# usbdist.net
KiCad netlist of a schematic drawn in EAGLE
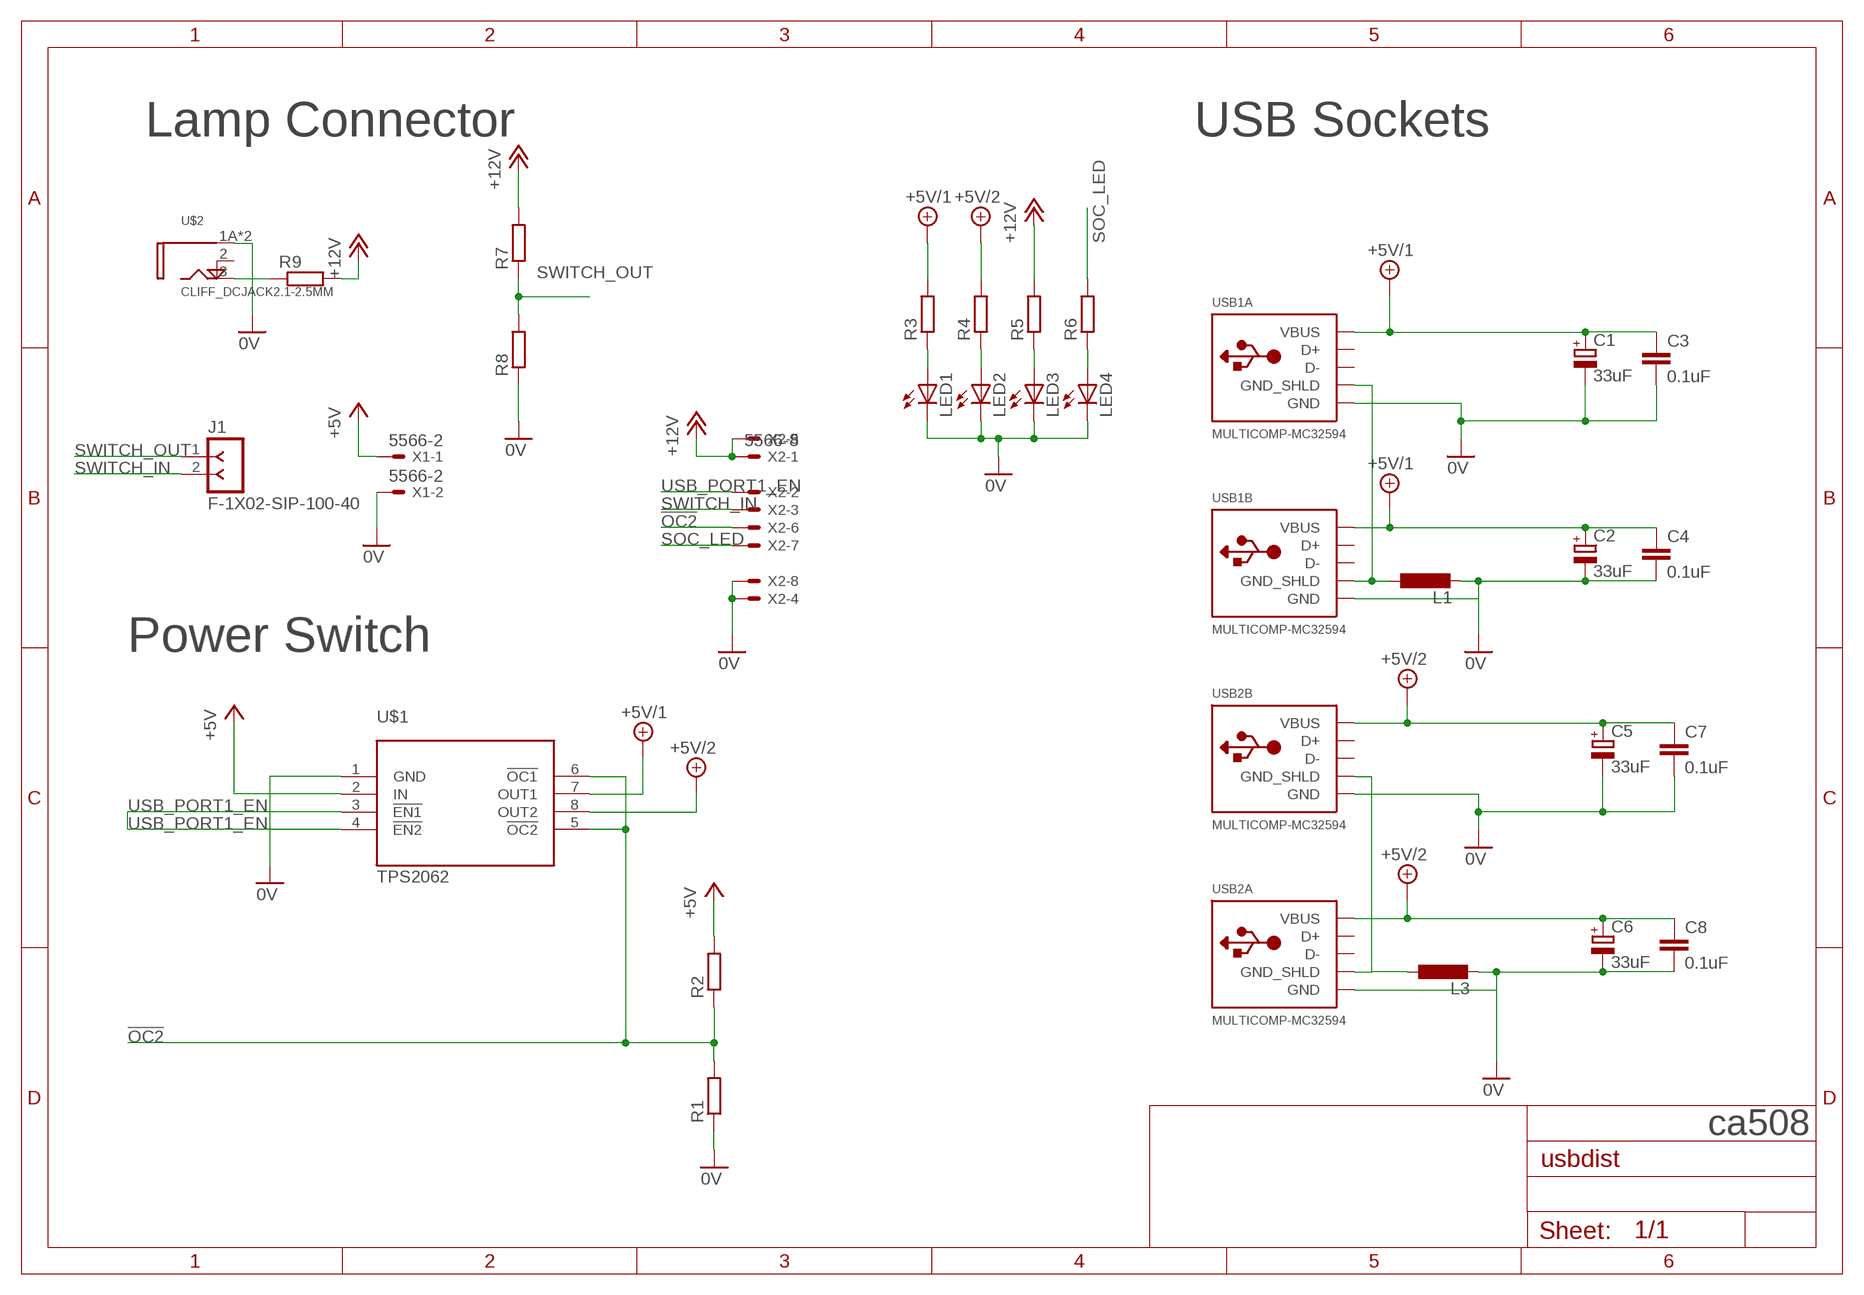
[diagram p0: schematic, sheet 1]

(export (version "E")
  (design (tool "Eeschema 10.0.6"))
  (components
    (comp (ref "C1")
      (value "33uF")
      (footprint "eagle-import:B_3528-21R")
      (libsource (lib "eagle-import") (part "CPOL-EUB/3528-21R"))
    )
    (comp (ref "C2")
      (value "33uF")
      (footprint "eagle-import:B_3528-21R")
      (libsource (lib "eagle-import") (part "CPOL-EUB/3528-21R"))
    )
    (comp (ref "C3")
      (value "0.1uF")
      (footprint "eagle-import:C0603")
      (libsource (lib "eagle-import") (part "C-EUC0603"))
    )
    (comp (ref "C4")
      (value "0.1uF")
      (footprint "eagle-import:C0603")
      (libsource (lib "eagle-import") (part "C-EUC0603"))
    )
    (comp (ref "C5")
      (value "33uF")
      (footprint "eagle-import:B_3528-21R")
      (libsource (lib "eagle-import") (part "CPOL-EUB/3528-21R"))
    )
    (comp (ref "C6")
      (value "33uF")
      (footprint "eagle-import:B_3528-21R")
      (libsource (lib "eagle-import") (part "CPOL-EUB/3528-21R"))
    )
    (comp (ref "C7")
      (value "0.1uF")
      (footprint "eagle-import:C0603")
      (libsource (lib "eagle-import") (part "C-EUC0603"))
    )
    (comp (ref "C8")
      (value "0.1uF")
      (footprint "eagle-import:C0603")
      (libsource (lib "eagle-import") (part "C-EUC0603"))
    )
    (comp (ref "J1")
      (value "F-1X02-SIP-100-40")
      (footprint "eagle-import:SIP-100-02-40")
      (libsource (lib "eagle-import") (part "F-1X02-SIP-100-40"))
    )
    (comp (ref "L1")
      (value "L-EUL2012C")
      (footprint "eagle-import:L2012C")
      (libsource (lib "eagle-import") (part "L-EUL2012C"))
    )
    (comp (ref "L3")
      (value "L-EUL2012C")
      (footprint "eagle-import:L2012C")
      (libsource (lib "eagle-import") (part "L-EUL2012C"))
    )
    (comp (ref "LED1")
      (value "LEDCHIP-LED0805")
      (footprint "eagle-import:CHIP-LED0805")
      (libsource (lib "eagle-import") (part "LEDCHIP-LED0805"))
    )
    (comp (ref "LED2")
      (value "LEDCHIP-LED0805")
      (footprint "eagle-import:CHIP-LED0805")
      (libsource (lib "eagle-import") (part "LEDCHIP-LED0805"))
    )
    (comp (ref "LED3")
      (value "LEDCHIP-LED0805")
      (footprint "eagle-import:CHIP-LED0805")
      (libsource (lib "eagle-import") (part "LEDCHIP-LED0805"))
    )
    (comp (ref "LED4")
      (value "LEDCHIP-LED0805")
      (footprint "eagle-import:CHIP-LED0805")
      (libsource (lib "eagle-import") (part "LEDCHIP-LED0805"))
    )
    (comp (ref "R1")
      (value "R-EU_R0805")
      (footprint "eagle-import:R0805")
      (libsource (lib "eagle-import") (part "R-EU_R0805"))
    )
    (comp (ref "R2")
      (value "R-EU_R0805")
      (footprint "eagle-import:R0805")
      (libsource (lib "eagle-import") (part "R-EU_R0805"))
    )
    (comp (ref "R3")
      (value "R-EU_R0805")
      (footprint "eagle-import:R0805")
      (libsource (lib "eagle-import") (part "R-EU_R0805"))
    )
    (comp (ref "R4")
      (value "R-EU_R0805")
      (footprint "eagle-import:R0805")
      (libsource (lib "eagle-import") (part "R-EU_R0805"))
    )
    (comp (ref "R5")
      (value "R-EU_R0805")
      (footprint "eagle-import:R0805")
      (libsource (lib "eagle-import") (part "R-EU_R0805"))
    )
    (comp (ref "R6")
      (value "R-EU_R0805")
      (footprint "eagle-import:R0805")
      (libsource (lib "eagle-import") (part "R-EU_R0805"))
    )
    (comp (ref "R7")
      (value "R-EU_R0805")
      (footprint "eagle-import:R0805")
      (libsource (lib "eagle-import") (part "R-EU_R0805"))
    )
    (comp (ref "R8")
      (value "R-EU_R0805")
      (footprint "eagle-import:R0805")
      (libsource (lib "eagle-import") (part "R-EU_R0805"))
    )
    (comp (ref "R9")
      (value "R-EU_0204/5")
      (footprint "eagle-import:0204_5")
      (libsource (lib "eagle-import") (part "R-EU_0204/5"))
    )
    (comp (ref "U$1")
      (value "TPS2062")
      (footprint "eagle-import:SO8")
      (libsource (lib "eagle-import") (part "TPS2062"))
    )
    (comp (ref "U$2")
      (value "CLIFF_DCJACK2.1-2.5MM")
      (footprint "eagle-import:FC6814XS")
      (libsource (lib "eagle-import") (part "CLIFF_DCJACK2.1-2.5MM"))
    )
    (comp (ref "USB1")
      (value "MULTICOMP-MC32594")
      (footprint "eagle-import:MC32594")
      (libsource (lib "eagle-import") (part "MULTICOMP-MC32594"))
    )
    (comp (ref "USB2")
      (value "MULTICOMP-MC32594")
      (footprint "eagle-import:MC32594")
      (libsource (lib "eagle-import") (part "MULTICOMP-MC32594"))
    )
    (comp (ref "X1")
      (value "5566-2")
      (footprint "eagle-import:5566-2")
      (libsource (lib "eagle-import") (part "5566-2"))
    )
    (comp (ref "X2")
      (value "5566-8")
      (footprint "eagle-import:5566-8")
      (libsource (lib "eagle-import") (part "5566-8"))
    )
  )
  (nets
    (net (code "1") (name "+5V") (class "Default")
      (node (ref "R2") (pin "2") (pinfunction "2_2") (pintype "passive"))
      (node (ref "U$1") (pin "2") (pinfunction "IN_2") (pintype "input"))
      (node (ref "X1") (pin "1") (pinfunction "S_1") (pintype "passive"))
    )
    (net (code "2") (name "+5V{slash}1") (class "Default")
      (node (ref "C1") (pin "+") (pinfunction "+_+") (pintype "passive"))
      (node (ref "C2") (pin "+") (pinfunction "+_+") (pintype "passive"))
      (node (ref "C3") (pin "1") (pinfunction "1_1") (pintype "passive"))
      (node (ref "C4") (pin "1") (pinfunction "1_1") (pintype "passive"))
      (node (ref "R3") (pin "2") (pinfunction "2_2") (pintype "passive"))
      (node (ref "U$1") (pin "7") (pinfunction "OUT1_7") (pintype "passive"))
      (node (ref "USB1") (pin "USB1-1") (pinfunction "VBUS_USB1-1") (pintype "power_in"))
      (node (ref "USB1") (pin "USB2-1") (pinfunction "VBUS_USB2-1") (pintype "power_in"))
    )
    (net (code "3") (name "+5V{slash}2") (class "Default")
      (node (ref "C5") (pin "+") (pinfunction "+_+") (pintype "passive"))
      (node (ref "C6") (pin "+") (pinfunction "+_+") (pintype "passive"))
      (node (ref "C7") (pin "1") (pinfunction "1_1") (pintype "passive"))
      (node (ref "C8") (pin "1") (pinfunction "1_1") (pintype "passive"))
      (node (ref "R4") (pin "2") (pinfunction "2_2") (pintype "passive"))
      (node (ref "U$1") (pin "8") (pinfunction "OUT2_8") (pintype "passive"))
      (node (ref "USB2") (pin "USB1-1") (pinfunction "VBUS_USB1-1") (pintype "power_in"))
      (node (ref "USB2") (pin "USB2-1") (pinfunction "VBUS_USB2-1") (pintype "power_in"))
    )
    (net (code "4") (name "+12V") (class "Default")
      (node (ref "R5") (pin "2") (pinfunction "2_2") (pintype "passive"))
      (node (ref "R7") (pin "2") (pinfunction "2_2") (pintype "passive"))
      (node (ref "R9") (pin "2") (pinfunction "2_2") (pintype "passive"))
      (node (ref "X2") (pin "1") (pinfunction "S_1") (pintype "passive"))
      (node (ref "X2") (pin "5") (pinfunction "S_5") (pintype "passive"))
    )
    (net (code "5") (name "/SHUNT") (class "Default")
      (node (ref "U$2") (pin "2") (pinfunction "SHUNT_2") (pintype "power_in"))
    )
    (net (code "6") (name "/SOC_LED") (class "Default")
      (node (ref "R6") (pin "2") (pinfunction "2_2") (pintype "passive"))
      (node (ref "X2") (pin "7") (pinfunction "S_7") (pintype "passive"))
    )
    (net (code "7") (name "/SWITCH_IN") (class "Default")
      (node (ref "J1") (pin "2") (pinfunction "2_2") (pintype "passive"))
      (node (ref "X2") (pin "3") (pinfunction "S_3") (pintype "passive"))
    )
    (net (code "8") (name "/SWITCH_OUT") (class "Default")
      (node (ref "J1") (pin "1") (pinfunction "1_1") (pintype "passive"))
      (node (ref "R7") (pin "1") (pinfunction "1_1") (pintype "passive"))
      (node (ref "R8") (pin "2") (pinfunction "2_2") (pintype "passive"))
    )
    (net (code "9") (name "/USB_PORT1_EN") (class "Default")
      (node (ref "U$1") (pin "3") (pinfunction "~{EN1}_3") (pintype "input"))
      (node (ref "U$1") (pin "4") (pinfunction "~{EN2}_4") (pintype "input"))
      (node (ref "X2") (pin "2") (pinfunction "S_2") (pintype "passive"))
    )
    (net (code "10") (name "/~{OC2}") (class "Default")
      (node (ref "R1") (pin "2") (pinfunction "2_2") (pintype "passive"))
      (node (ref "R2") (pin "1") (pinfunction "1_1") (pintype "passive"))
      (node (ref "U$1") (pin "5") (pinfunction "~{OC2}_5") (pintype "power_in"))
      (node (ref "U$1") (pin "6") (pinfunction "~{OC1}_6") (pintype "passive"))
      (node (ref "X2") (pin "6") (pinfunction "S_6") (pintype "passive"))
    )
    (net (code "11") (name "0V") (class "Default")
      (node (ref "C1") (pin "-") (pinfunction "-_-") (pintype "passive"))
      (node (ref "C2") (pin "-") (pinfunction "-_-") (pintype "passive"))
      (node (ref "C3") (pin "2") (pinfunction "2_2") (pintype "passive"))
      (node (ref "C4") (pin "2") (pinfunction "2_2") (pintype "passive"))
      (node (ref "C5") (pin "-") (pinfunction "-_-") (pintype "passive"))
      (node (ref "C6") (pin "-") (pinfunction "-_-") (pintype "passive"))
      (node (ref "C7") (pin "2") (pinfunction "2_2") (pintype "passive"))
      (node (ref "C8") (pin "2") (pinfunction "2_2") (pintype "passive"))
      (node (ref "L1") (pin "2") (pinfunction "2_2") (pintype "passive"))
      (node (ref "L3") (pin "2") (pinfunction "2_2") (pintype "passive"))
      (node (ref "LED1") (pin "C") (pinfunction "C_C") (pintype "passive"))
      (node (ref "LED2") (pin "C") (pinfunction "C_C") (pintype "passive"))
      (node (ref "LED3") (pin "C") (pinfunction "C_C") (pintype "passive"))
      (node (ref "LED4") (pin "C") (pinfunction "C_C") (pintype "passive"))
      (node (ref "R1") (pin "1") (pinfunction "1_1") (pintype "passive"))
      (node (ref "R8") (pin "1") (pinfunction "1_1") (pintype "passive"))
      (node (ref "U$1") (pin "1") (pinfunction "GND_1") (pintype "input"))
      (node (ref "U$2") (pin "1A") (pinfunction "SLEEVE_1A") (pintype "power_in"))
      (node (ref "U$2") (pin "1B") (pinfunction "SLEEVE_1B") (pintype "power_in"))
      (node (ref "USB1") (pin "USB1-4") (pinfunction "GND_USB1-4") (pintype "power_in"))
      (node (ref "USB1") (pin "USB2-4") (pinfunction "GND_USB2-4") (pintype "power_in"))
      (node (ref "USB2") (pin "USB1-4") (pinfunction "GND_USB1-4") (pintype "power_in"))
      (node (ref "USB2") (pin "USB2-4") (pinfunction "GND_USB2-4") (pintype "power_in"))
      (node (ref "X1") (pin "2") (pinfunction "S_2") (pintype "passive"))
      (node (ref "X2") (pin "4") (pinfunction "S_4") (pintype "passive"))
      (node (ref "X2") (pin "8") (pinfunction "S_8") (pintype "passive"))
    )
    (net (code "12") (name "Net-(L1-Pad1)") (class "Default")
      (node (ref "L1") (pin "1") (pinfunction "1_1") (pintype "passive"))
      (node (ref "USB1") (pin "P$1") (pinfunction "GND_SHLD_P$1") (pintype "power_in"))
      (node (ref "USB1") (pin "P$2") (pinfunction "GND_SHLD_P$2") (pintype "power_in"))
      (node (ref "USB1") (pin "P$3") (pinfunction "GND_SHLD_P$3") (pintype "power_in"))
      (node (ref "USB1") (pin "P$4") (pinfunction "GND_SHLD_P$4") (pintype "power_in"))
    )
    (net (code "13") (name "Net-(L3-Pad1)") (class "Default")
      (node (ref "L3") (pin "1") (pinfunction "1_1") (pintype "passive"))
      (node (ref "USB2") (pin "P$1") (pinfunction "GND_SHLD_P$1") (pintype "power_in"))
      (node (ref "USB2") (pin "P$2") (pinfunction "GND_SHLD_P$2") (pintype "power_in"))
      (node (ref "USB2") (pin "P$3") (pinfunction "GND_SHLD_P$3") (pintype "power_in"))
      (node (ref "USB2") (pin "P$4") (pinfunction "GND_SHLD_P$4") (pintype "power_in"))
    )
    (net (code "14") (name "Net-(LED1-PadA)") (class "Default")
      (node (ref "LED1") (pin "A") (pinfunction "A_A") (pintype "passive"))
      (node (ref "R3") (pin "1") (pinfunction "1_1") (pintype "passive"))
    )
    (net (code "15") (name "Net-(LED2-PadA)") (class "Default")
      (node (ref "LED2") (pin "A") (pinfunction "A_A") (pintype "passive"))
      (node (ref "R4") (pin "1") (pinfunction "1_1") (pintype "passive"))
    )
    (net (code "16") (name "Net-(LED3-PadA)") (class "Default")
      (node (ref "LED3") (pin "A") (pinfunction "A_A") (pintype "passive"))
      (node (ref "R5") (pin "1") (pinfunction "1_1") (pintype "passive"))
    )
    (net (code "17") (name "Net-(LED4-PadA)") (class "Default")
      (node (ref "LED4") (pin "A") (pinfunction "A_A") (pintype "passive"))
      (node (ref "R6") (pin "1") (pinfunction "1_1") (pintype "passive"))
    )
    (net (code "18") (name "Net-(U$2-TIP)") (class "Default")
      (node (ref "R9") (pin "1") (pinfunction "1_1") (pintype "passive"))
      (node (ref "U$2") (pin "3") (pinfunction "TIP_3") (pintype "power_in"))
    )
    (net (code "19") (name "unconnected-(USB1A-D+-PadUSB1-3)") (class "Default")
      (node (ref "USB1") (pin "USB1-3") (pinfunction "D+_USB1-3") (pintype "bidirectional"))
    )
    (net (code "20") (name "unconnected-(USB1A-D--PadUSB1-2)") (class "Default")
      (node (ref "USB1") (pin "USB1-2") (pinfunction "D-_USB1-2") (pintype "bidirectional"))
    )
    (net (code "21") (name "unconnected-(USB1B-D+-PadUSB2-3)") (class "Default")
      (node (ref "USB1") (pin "USB2-3") (pinfunction "D+_USB2-3") (pintype "bidirectional"))
    )
    (net (code "22") (name "unconnected-(USB1B-D--PadUSB2-2)") (class "Default")
      (node (ref "USB1") (pin "USB2-2") (pinfunction "D-_USB2-2") (pintype "bidirectional"))
    )
    (net (code "23") (name "unconnected-(USB2A-D+-PadUSB1-3)") (class "Default")
      (node (ref "USB2") (pin "USB1-3") (pinfunction "D+_USB1-3") (pintype "bidirectional"))
    )
    (net (code "24") (name "unconnected-(USB2A-D--PadUSB1-2)") (class "Default")
      (node (ref "USB2") (pin "USB1-2") (pinfunction "D-_USB1-2") (pintype "bidirectional"))
    )
    (net (code "25") (name "unconnected-(USB2B-D+-PadUSB2-3)") (class "Default")
      (node (ref "USB2") (pin "USB2-3") (pinfunction "D+_USB2-3") (pintype "bidirectional"))
    )
    (net (code "26") (name "unconnected-(USB2B-D--PadUSB2-2)") (class "Default")
      (node (ref "USB2") (pin "USB2-2") (pinfunction "D-_USB2-2") (pintype "bidirectional"))
    )
  )
)
